# Main_Circuit.net
KiCad netlist of a schematic drawn in Altium Designer
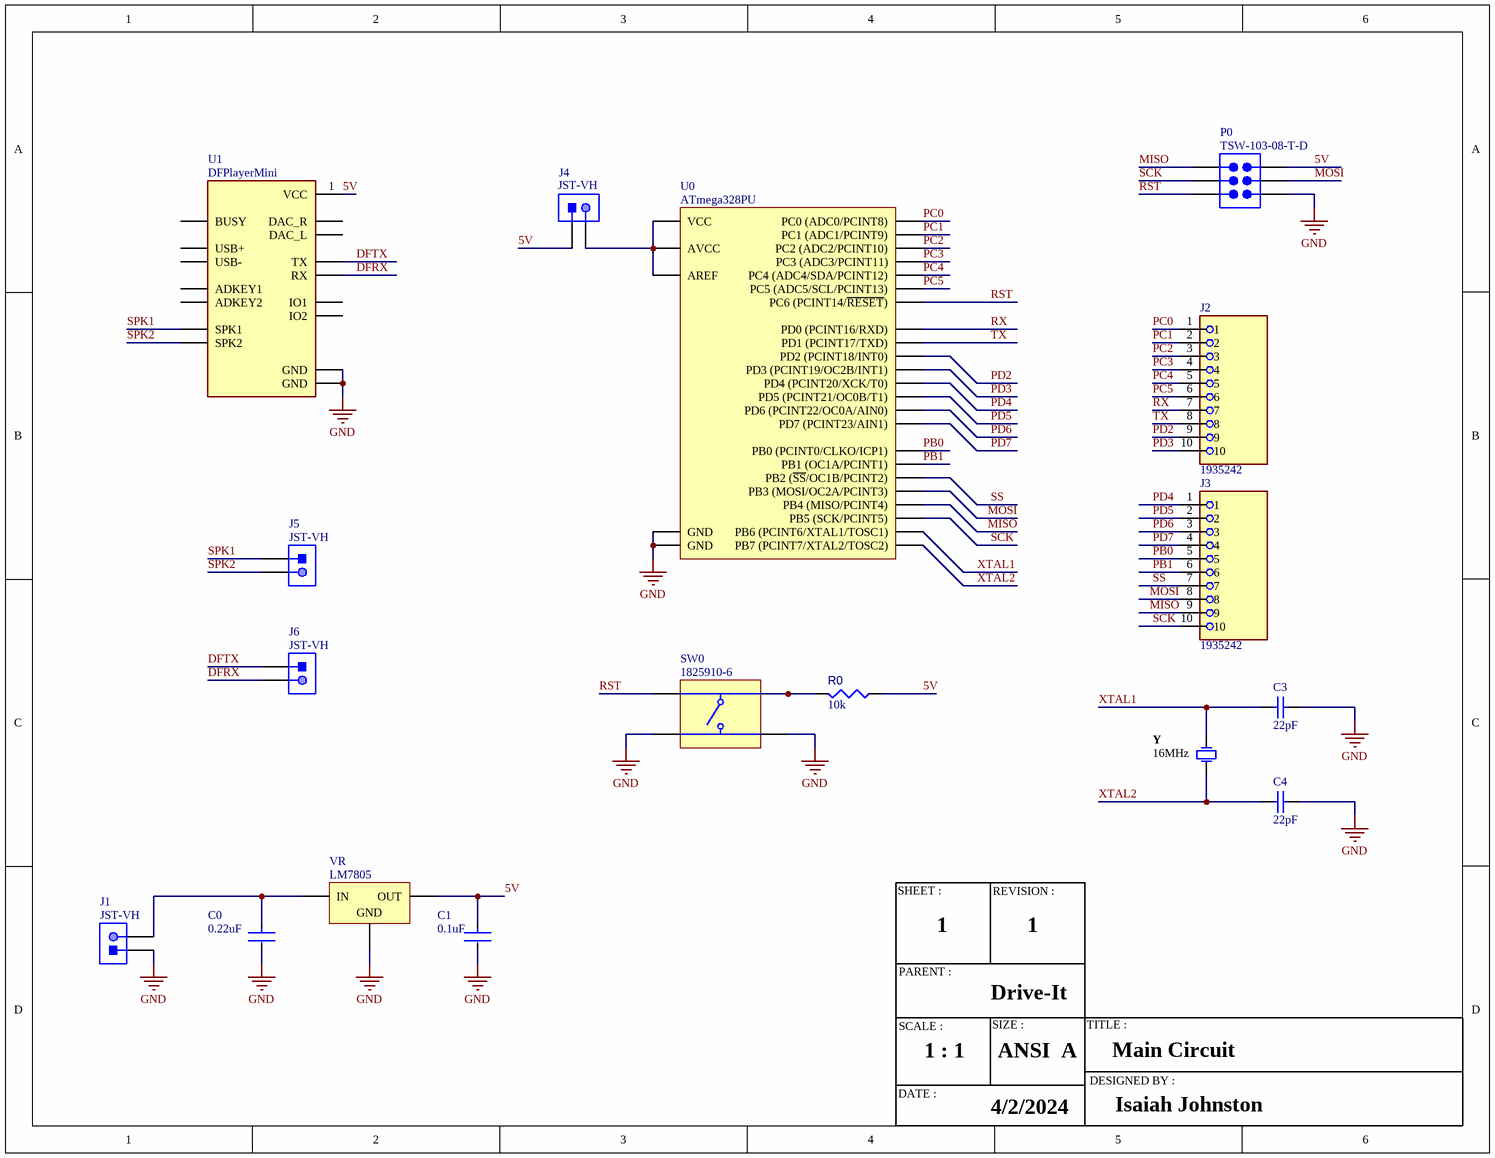
[diagram p0: Main_Circuit.SchDoc]

(export (version "E")
  (design (tool "Eeschema 10.0.6"))
  (components
    (comp (ref "C0")
      (value "0.22uF")
      (footprint "FP-RCE1K1-2_5-MFG")
      (description "Cap Ceramic Monolithic 220nF 50V 10% Thru-Hole Bulk")
      (fields (field (name "TOLERANCE") "10%"))
      (libsource (lib "Altium Content Vault") (part "02cd4be3c70576c341d710602a673aa"))
    )
    (comp (ref "C1")
      (value "0.1uF")
      (footprint "FP-K15H5-MFG")
      (description "CAP CER 0.1UF 50V X7R RADIAL")
      (fields (field (name "VOLTAGE") "50V") (field (name "TOLERANCE") "10%"))
      (libsource (lib "Altium Content Vault") (part "11868f565c42a9108669ba33697ecf6"))
    )
    (comp (ref "C3")
      (value "22pF")
      (footprint "KEMT-C315-THT-2")
      (description "Capacitor, Ceramic, 22 pF, +/-10 %, 100 V, -55 to 125 degC, 2-Pin THD, RoHS, Bulk")
      (libsource (lib "Altium Content Vault") (part "CAP-NP-2"))
    )
    (comp (ref "C4")
      (value "22pF")
      (footprint "KEMT-C315-THT-2")
      (description "Capacitor, Ceramic, 22 pF, +/-10 %, 100 V, -55 to 125 degC, 2-Pin THD, RoHS, Bulk")
      (libsource (lib "Altium Content Vault") (part "CAP-NP-2"))
    )
    (comp (ref "J1")
      (value "JST-VH")
      (footprint "JST-B2P-VH(LF)(SN)_V")
      (fields (field (name "MANUFACTURER") "JST"))
      (libsource (lib "") (part "CN-1P-M-R2_2"))
    )
    (comp (ref "J2")
      (value "1935242")
      (footprint "PHOENIX_1935242")
      (description "PCB Terminal Screw 5mm 16AWG 400V 17.5A 10 Position COMBICON PT Series ¦ Phoenix Contact 1935242")
      (fields (field (name "MF") "Phoenix Contact"))
      (libsource (lib "1935242 (1)") (part "1935242"))
    )
    (comp (ref "J3")
      (value "1935242")
      (footprint "PHOENIX_1935242")
      (description "PCB Terminal Screw 5mm 16AWG 400V 17.5A 10 Position COMBICON PT Series ¦ Phoenix Contact 1935242")
      (fields (field (name "MF") "Phoenix Contact"))
      (libsource (lib "1935242 (1)") (part "1935242"))
    )
    (comp (ref "J4")
      (value "JST-VH")
      (footprint "JST-B2P-VH(LF)(SN)_V")
      (fields (field (name "MANUFACTURER") "JST"))
      (libsource (lib "University of Pittsburgh") (part "CN-1P-M-R2"))
    )
    (comp (ref "J5")
      (value "JST-VH")
      (footprint "JST-B2P-VH(LF)(SN)_V")
      (fields (field (name "MANUFACTURER") "JST"))
      (libsource (lib "") (part "CN-1P-M-R2_1"))
    )
    (comp (ref "J6")
      (value "JST-VH")
      (footprint "JST-B2P-VH(LF)(SN)_V")
      (fields (field (name "MANUFACTURER") "JST"))
      (libsource (lib "") (part "CN-1P-M-R2_1"))
    )
    (comp (ref "P0")
      (value "TSW-103-08-T-D")
      (footprint "SMTC-TSW-103-08-X-D")
      (description "0.025\" SQ Post Header, Through-hole, Vertical, -55 to 105 degC, 2.54 mm Pitch, 6-Pin, Male, RoHS")
      (fields (field (name "MANUFACTURER") "Samtec"))
      (libsource (lib "Altium Content Vault") (part "SMTC-TSW-103-08-X-D"))
    )
    (comp (ref "R0")
      (value "10k")
      (footprint "RESA60-630X240")
      (description "Axial Resistor, 10 KOhm, +/- 1%, 0.25 W, -55 to 155 degC, 2-Pin THD, RoHS, Bulk")
      (fields (field (name "TOLERANCE") "1%") (field (name "POWER") "250mW"))
      (libsource (lib "University of Pittsburgh") (part "RES-2"))
    )
    (comp (ref "SW0")
      (value "1825910-6")
      (footprint "TECO-1825910-6_V")
      (description "Tact Switch, SPST-NO, 0.05 A, -35 to 85 degC, 4-Pin THD, RoHS, Bulk")
      (fields (field (name "MANUFACTURER") "TE Connectivity"))
      (libsource (lib "Altium Content Vault") (part "SW-SPST-4_A"))
    )
    (comp (ref "U0")
      (value "ATmega328PU")
      (footprint "ATML-28P3")
      (fields (field (name "MANUFACTURER") "Atmel"))
      (libsource (lib "University of Pittsburgh") (part "MC-8B-ATM48-IL28"))
    )
    (comp (ref "U1")
      (value "DFPlayerMini")
      (footprint "MODULE_DFR0299")
      (description "Dfplayer - a Mini Mp3 Player")
      (fields (field (name "MP") "DFR0299"))
      (libsource (lib "DFR0299") (part "DFR0299"))
    )
    (comp (ref "VR")
      (value "LM7805")
      (footprint "FAIR-TO-220-3")
      (description "Positive Voltage Regulator, 5 V, 1 A, -40 to 125 degC, 3-Pin TO-220, RoHS, Tube")
      (fields (field (name "MANUFACTURER") "FairchildSemiconductor"))
      (libsource (lib "Altium Content Vault") (part "FAIR-LM7805CT-TO220-3"))
    )
    (comp (ref "Y")
      (value "16MHz")
      (footprint "FOX-FOXSLF160-20")
      (description "Resistance Weld Thru-Hole Crystal, 16 MHz, -20 to 70 degC, 2-Pin THD, RoHS, Bulk")
      (fields (field (name "TOLERANCE") "1%"))
      (libsource (lib "Altium Content Vault") (part "XTAL-1-2-2"))
    )
  )
  (nets
    (net (code "1") (name "/5V") (class "Default")
      (node (ref "C1") (pin "1") (pinfunction "1_1") (pintype "passive"))
      (node (ref "J4") (pin "1") (pinfunction "1_1") (pintype "passive"))
      (node (ref "P0") (pin "5") (pinfunction "5_5") (pintype "passive"))
      (node (ref "R0") (pin "1") (pinfunction "1_1") (pintype "passive"))
      (node (ref "U1") (pin "1") (pinfunction "VCC_1") (pintype "passive"))
      (node (ref "VR") (pin "3") (pinfunction "OUT_3") (pintype "passive"))
    )
    (net (code "2") (name "/DFRX") (class "Default")
      (node (ref "J6") (pin "2") (pinfunction "2_2") (pintype "passive"))
      (node (ref "U1") (pin "2") (pinfunction "RX_2") (pintype "passive"))
    )
    (net (code "3") (name "/DFTX") (class "Default")
      (node (ref "J6") (pin "1") (pinfunction "1_1") (pintype "passive"))
      (node (ref "U1") (pin "3") (pinfunction "TX_3") (pintype "passive"))
    )
    (net (code "4") (name "/MISO") (class "Default")
      (node (ref "J3") (pin "9") (pinfunction "9_9") (pintype "passive"))
      (node (ref "P0") (pin "6") (pinfunction "6_6") (pintype "passive"))
      (node (ref "U0") (pin "18") (pinfunction "PB4_(MISO/PCINT4)_18") (pintype "passive"))
    )
    (net (code "5") (name "/MOSI") (class "Default")
      (node (ref "J3") (pin "8") (pinfunction "8_8") (pintype "passive"))
      (node (ref "P0") (pin "3") (pinfunction "3_3") (pintype "passive"))
      (node (ref "U0") (pin "17") (pinfunction "PB3_(MOSI/OC2A/PCINT3)_17") (pintype "passive"))
    )
    (net (code "6") (name "/PB0") (class "Default")
      (node (ref "J3") (pin "5") (pinfunction "5_5") (pintype "passive"))
      (node (ref "U0") (pin "14") (pinfunction "PB0_(PCINT0/CLKO/ICP1)_14") (pintype "passive"))
    )
    (net (code "7") (name "/PB1") (class "Default")
      (node (ref "J3") (pin "6") (pinfunction "6_6") (pintype "passive"))
      (node (ref "U0") (pin "15") (pinfunction "PB1_(OC1A/PCINT1)_15") (pintype "passive"))
    )
    (net (code "8") (name "/PC0") (class "Default")
      (node (ref "J2") (pin "1") (pinfunction "1_1") (pintype "passive"))
      (node (ref "U0") (pin "23") (pinfunction "PC0_(ADC0/PCINT8)_23") (pintype "passive"))
    )
    (net (code "9") (name "/PC1") (class "Default")
      (node (ref "J2") (pin "2") (pinfunction "2_2") (pintype "passive"))
      (node (ref "U0") (pin "24") (pinfunction "PC1_(ADC1/PCINT9)_24") (pintype "passive"))
    )
    (net (code "10") (name "/PC2") (class "Default")
      (node (ref "J2") (pin "3") (pinfunction "3_3") (pintype "passive"))
      (node (ref "U0") (pin "25") (pinfunction "PC2_(ADC2/PCINT10)_25") (pintype "passive"))
    )
    (net (code "11") (name "/PC3") (class "Default")
      (node (ref "J2") (pin "4") (pinfunction "4_4") (pintype "passive"))
      (node (ref "U0") (pin "26") (pinfunction "PC3_(ADC3/PCINT11)_26") (pintype "passive"))
    )
    (net (code "12") (name "/PC4") (class "Default")
      (node (ref "J2") (pin "5") (pinfunction "5_5") (pintype "passive"))
      (node (ref "U0") (pin "27") (pinfunction "PC4_(ADC4/SDA/PCINT12)_27") (pintype "passive"))
    )
    (net (code "13") (name "/PC5") (class "Default")
      (node (ref "J2") (pin "6") (pinfunction "6_6") (pintype "passive"))
      (node (ref "U0") (pin "28") (pinfunction "PC5_(ADC5/SCL/PCINT13)_28") (pintype "passive"))
    )
    (net (code "14") (name "/PD2") (class "Default")
      (node (ref "J2") (pin "9") (pinfunction "9_9") (pintype "passive"))
      (node (ref "U0") (pin "4") (pinfunction "PD2_(PCINT18/INT0)_4") (pintype "passive"))
    )
    (net (code "15") (name "/PD3") (class "Default")
      (node (ref "J2") (pin "10") (pinfunction "10_10") (pintype "passive"))
      (node (ref "U0") (pin "5") (pinfunction "PD3_(PCINT19/OC2B/INT1)_5") (pintype "passive"))
    )
    (net (code "16") (name "/PD4") (class "Default")
      (node (ref "J3") (pin "1") (pinfunction "1_1") (pintype "passive"))
      (node (ref "U0") (pin "6") (pinfunction "PD4_(PCINT20/XCK/T0)_6") (pintype "passive"))
    )
    (net (code "17") (name "/PD5") (class "Default")
      (node (ref "J3") (pin "2") (pinfunction "2_2") (pintype "passive"))
      (node (ref "U0") (pin "11") (pinfunction "PD5_(PCINT21/OC0B/T1)_11") (pintype "passive"))
    )
    (net (code "18") (name "/PD6") (class "Default")
      (node (ref "J3") (pin "3") (pinfunction "3_3") (pintype "passive"))
      (node (ref "U0") (pin "12") (pinfunction "PD6_(PCINT22/OC0A/AIN0)_12") (pintype "passive"))
    )
    (net (code "19") (name "/PD7") (class "Default")
      (node (ref "J3") (pin "4") (pinfunction "4_4") (pintype "passive"))
      (node (ref "U0") (pin "13") (pinfunction "PD7_(PCINT23/AIN1)_13") (pintype "passive"))
    )
    (net (code "20") (name "/RST") (class "Default")
      (node (ref "P0") (pin "2") (pinfunction "2_2") (pintype "passive"))
      (node (ref "SW0") (pin "1") (pinfunction "1_1") (pintype "passive"))
      (node (ref "U0") (pin "1") (pinfunction "PC6_(PCINT14/~{RESET})_1") (pintype "passive"))
    )
    (net (code "21") (name "/RX") (class "Default")
      (node (ref "J2") (pin "7") (pinfunction "7_7") (pintype "passive"))
      (node (ref "U0") (pin "2") (pinfunction "PD0_(PCINT16/RXD)_2") (pintype "passive"))
    )
    (net (code "22") (name "/SCK") (class "Default")
      (node (ref "J3") (pin "10") (pinfunction "10_10") (pintype "passive"))
      (node (ref "P0") (pin "4") (pinfunction "4_4") (pintype "passive"))
      (node (ref "U0") (pin "19") (pinfunction "PB5_(SCK/PCINT5)_19") (pintype "passive"))
    )
    (net (code "23") (name "/SPK1") (class "Default")
      (node (ref "J5") (pin "1") (pinfunction "1_1") (pintype "passive"))
      (node (ref "U1") (pin "6") (pinfunction "SPK1_6") (pintype "passive"))
    )
    (net (code "24") (name "/SPK2") (class "Default")
      (node (ref "J5") (pin "2") (pinfunction "2_2") (pintype "passive"))
      (node (ref "U1") (pin "8") (pinfunction "SPK2_8") (pintype "passive"))
    )
    (net (code "25") (name "/SS") (class "Default")
      (node (ref "J3") (pin "7") (pinfunction "7_7") (pintype "passive"))
      (node (ref "U0") (pin "16") (pinfunction "PB2_(~{SS}/OC1B/PCINT2)_16") (pintype "passive"))
    )
    (net (code "26") (name "/TX") (class "Default")
      (node (ref "J2") (pin "8") (pinfunction "8_8") (pintype "passive"))
      (node (ref "U0") (pin "3") (pinfunction "PD1_(PCINT17/TXD)_3") (pintype "passive"))
    )
    (net (code "27") (name "/XTAL1") (class "Default")
      (node (ref "C3") (pin "1") (pinfunction "1_1") (pintype "passive"))
      (node (ref "U0") (pin "9") (pinfunction "PB6_(PCINT6/XTAL1/TOSC1)_9") (pintype "passive"))
      (node (ref "Y") (pin "2") (pinfunction "2_2") (pintype "passive"))
    )
    (net (code "28") (name "/XTAL2") (class "Default")
      (node (ref "C4") (pin "1") (pinfunction "1_1") (pintype "passive"))
      (node (ref "U0") (pin "10") (pinfunction "PB7_(PCINT7/XTAL2/TOSC2)_10") (pintype "passive"))
      (node (ref "Y") (pin "1") (pinfunction "1_1") (pintype "passive"))
    )
    (net (code "29") (name "GND") (class "Default")
      (node (ref "C0") (pin "2") (pinfunction "2_2") (pintype "passive"))
      (node (ref "C1") (pin "2") (pinfunction "2_2") (pintype "passive"))
      (node (ref "C3") (pin "2") (pinfunction "2_2") (pintype "passive"))
      (node (ref "C4") (pin "2") (pinfunction "2_2") (pintype "passive"))
      (node (ref "J1") (pin "1") (pinfunction "1_1") (pintype "passive"))
      (node (ref "P0") (pin "1") (pinfunction "1_1") (pintype "passive"))
      (node (ref "SW0") (pin "3") (pinfunction "3_3") (pintype "passive"))
      (node (ref "SW0") (pin "4") (pinfunction "4_4") (pintype "passive"))
      (node (ref "U0") (pin "22") (pinfunction "GND_22") (pintype "passive"))
      (node (ref "U0") (pin "8") (pinfunction "GND_8") (pintype "passive"))
      (node (ref "U1") (pin "10") (pinfunction "GND_10") (pintype "passive"))
      (node (ref "U1") (pin "7") (pinfunction "GND_7") (pintype "passive"))
      (node (ref "VR") (pin "2") (pinfunction "GND_2") (pintype "passive"))
    )
    (net (code "30") (name "Net-(R0-Pad2)") (class "Default")
      (node (ref "R0") (pin "2") (pinfunction "2_2") (pintype "passive"))
      (node (ref "SW0") (pin "2") (pinfunction "2_2") (pintype "passive"))
    )
    (net (code "31") (name "Net-(U0-AREF)") (class "Default")
      (node (ref "J4") (pin "2") (pinfunction "2_2") (pintype "passive"))
      (node (ref "U0") (pin "20") (pinfunction "AVCC_20") (pintype "passive"))
      (node (ref "U0") (pin "21") (pinfunction "AREF_21") (pintype "passive"))
      (node (ref "U0") (pin "7") (pinfunction "VCC_7") (pintype "passive"))
    )
    (net (code "32") (name "Net-(VR-IN)") (class "Default")
      (node (ref "C0") (pin "1") (pinfunction "1_1") (pintype "passive"))
      (node (ref "J1") (pin "2") (pinfunction "2_2") (pintype "passive"))
      (node (ref "VR") (pin "1") (pinfunction "IN_1") (pintype "passive"))
    )
    (net (code "33") (name "unconnected-(U1-ADKEY1-Pad12)") (class "Default")
      (node (ref "U1") (pin "12") (pinfunction "ADKEY1_12") (pintype "passive"))
    )
    (net (code "34") (name "unconnected-(U1-ADKEY2-Pad13)") (class "Default")
      (node (ref "U1") (pin "13") (pinfunction "ADKEY2_13") (pintype "passive"))
    )
    (net (code "35") (name "unconnected-(U1-BUSY-Pad16)") (class "Default")
      (node (ref "U1") (pin "16") (pinfunction "BUSY_16") (pintype "passive"))
    )
    (net (code "36") (name "unconnected-(U1-DAC_L-Pad5)") (class "Default")
      (node (ref "U1") (pin "5") (pinfunction "DAC_L_5") (pintype "passive"))
    )
    (net (code "37") (name "unconnected-(U1-DAC_R-Pad4)") (class "Default")
      (node (ref "U1") (pin "4") (pinfunction "DAC_R_4") (pintype "passive"))
    )
    (net (code "38") (name "unconnected-(U1-IO1-Pad9)") (class "Default")
      (node (ref "U1") (pin "9") (pinfunction "IO1_9") (pintype "passive"))
    )
    (net (code "39") (name "unconnected-(U1-IO2-Pad11)") (class "Default")
      (node (ref "U1") (pin "11") (pinfunction "IO2_11") (pintype "passive"))
    )
    (net (code "40") (name "unconnected-(U1-USB+-Pad14)") (class "Default")
      (node (ref "U1") (pin "14") (pinfunction "USB+_14") (pintype "passive"))
    )
    (net (code "41") (name "unconnected-(U1-USB--Pad15)") (class "Default")
      (node (ref "U1") (pin "15") (pinfunction "USB-_15") (pintype "passive"))
    )
  )
)
